# PowerLatch.net
KiCad netlist of a schematic drawn in Altium Designer
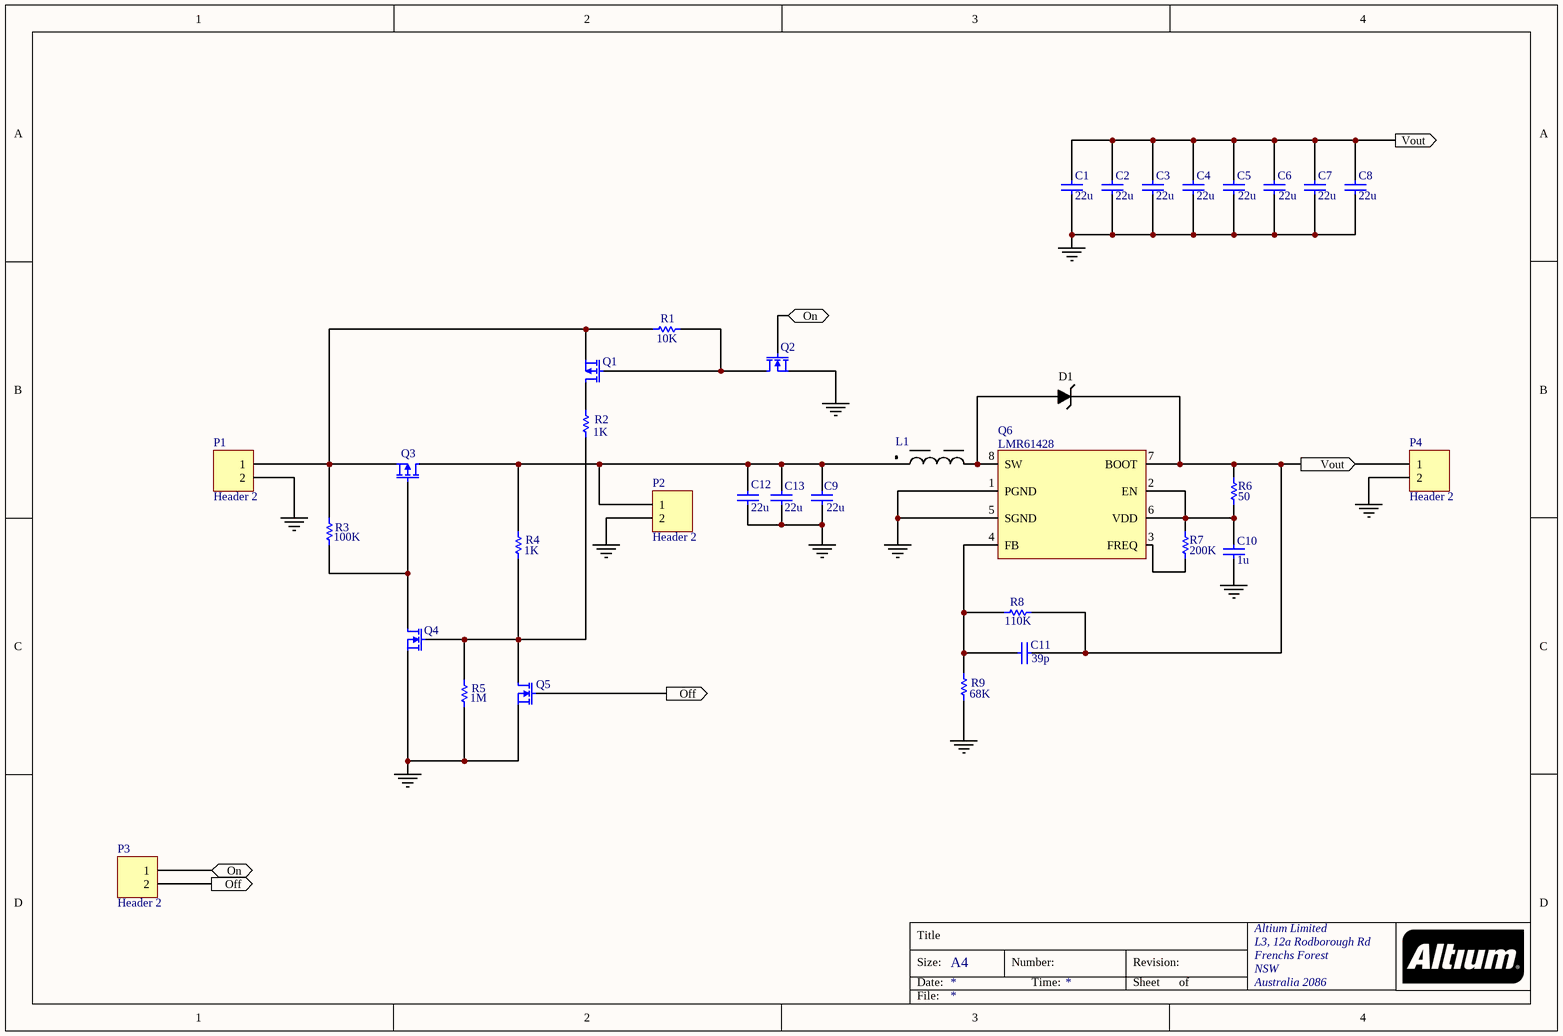
[diagram p0: PowerLatch.SchDoc]

(export (version "E")
  (design (tool "Eeschema 10.0.6"))
  (components
    (comp (ref "C1")
      (value "22u")
      (footprint "CAPC3225X28N")
      (description "Capacitor")
      (fields (field (name "Comment") "Cap") (field (name "PUBLISHER") "Altium Limited"))
      (libsource (lib "Miscellaneous Devices") (part "Cap"))
    )
    (comp (ref "C2")
      (value "22u")
      (footprint "CAPC3225X28N")
      (description "Capacitor")
      (fields (field (name "Comment") "Cap") (field (name "PUBLISHER") "Altium Limited"))
      (libsource (lib "Miscellaneous Devices") (part "Cap"))
    )
    (comp (ref "C3")
      (value "22u")
      (footprint "CAPC3225X28N")
      (description "Capacitor")
      (fields (field (name "Comment") "Cap") (field (name "PUBLISHER") "Altium Limited"))
      (libsource (lib "Miscellaneous Devices") (part "Cap"))
    )
    (comp (ref "C4")
      (value "22u")
      (footprint "CAPC3225X28N")
      (description "Capacitor")
      (fields (field (name "Comment") "Cap") (field (name "PUBLISHER") "Altium Limited"))
      (libsource (lib "Miscellaneous Devices") (part "Cap"))
    )
    (comp (ref "C5")
      (value "22u")
      (footprint "CAPC3225X28N")
      (description "Capacitor")
      (fields (field (name "Comment") "Cap") (field (name "PUBLISHER") "Altium Limited"))
      (libsource (lib "Miscellaneous Devices") (part "Cap"))
    )
    (comp (ref "C6")
      (value "22u")
      (footprint "CAPC3225X28N")
      (description "Capacitor")
      (fields (field (name "Comment") "Cap") (field (name "PUBLISHER") "Altium Limited"))
      (libsource (lib "Miscellaneous Devices") (part "Cap"))
    )
    (comp (ref "C7")
      (value "22u")
      (footprint "CAPC3225X28N")
      (description "Capacitor")
      (fields (field (name "Comment") "Cap") (field (name "PUBLISHER") "Altium Limited"))
      (libsource (lib "Miscellaneous Devices") (part "Cap"))
    )
    (comp (ref "C8")
      (value "22u")
      (footprint "CAPC3225X28N")
      (description "Capacitor")
      (fields (field (name "Comment") "Cap") (field (name "PUBLISHER") "Altium Limited"))
      (libsource (lib "Miscellaneous Devices") (part "Cap"))
    )
    (comp (ref "C9")
      (value "22u")
      (footprint "C1210_M")
      (description "Capacitor")
      (fields (field (name "Comment") "Cap") (field (name "PUBLISHER") "Altium Limited"))
      (libsource (lib "Miscellaneous Devices") (part "Cap"))
    )
    (comp (ref "C10")
      (value "1u")
      (footprint "C1210_M")
      (description "Capacitor")
      (fields (field (name "Comment") "Cap") (field (name "PUBLISHER") "Altium Limited"))
      (libsource (lib "Miscellaneous Devices") (part "Cap"))
    )
    (comp (ref "C11")
      (value "39p")
      (footprint "C1210_M")
      (description "Capacitor")
      (fields (field (name "Comment") "Cap") (field (name "PUBLISHER") "Altium Limited"))
      (libsource (lib "Miscellaneous Devices") (part "Cap"))
    )
    (comp (ref "C12")
      (value "22u")
      (footprint "C1210_M")
      (description "Capacitor")
      (fields (field (name "Comment") "Cap") (field (name "PUBLISHER") "Altium Limited"))
      (libsource (lib "Miscellaneous Devices") (part "Cap"))
    )
    (comp (ref "C13")
      (value "22u")
      (footprint "C1210_M")
      (description "Capacitor")
      (fields (field (name "Comment") "Cap") (field (name "PUBLISHER") "Altium Limited"))
      (libsource (lib "Miscellaneous Devices") (part "Cap"))
    )
    (comp (ref "D1")
      (value "Schottky")
      (footprint "DIOM4336X25N")
      (libsource (lib "Schlib1") (part "Schottky"))
    )
    (comp (ref "L1")
      (value "Inductor")
      (footprint "INDP120120X100N")
      (libsource (lib "Schlib1") (part "Inductor"))
    )
    (comp (ref "P1")
      (value "Header 2")
      (footprint "HDR1X2")
      (description "Header, 2-Pin")
      (fields (field (name "PUBLISHER") "Altium Limited"))
      (libsource (lib "Miscellaneous Connectors") (part "Header 2"))
    )
    (comp (ref "P2")
      (value "Header 2")
      (footprint "HDR1X2")
      (description "Header, 2-Pin")
      (fields (field (name "PUBLISHER") "Altium Limited"))
      (libsource (lib "") (part "Header 2_1"))
    )
    (comp (ref "P3")
      (value "Header 2")
      (footprint "HDR1X2")
      (description "Header, 2-Pin")
      (fields (field (name "PUBLISHER") "Altium Limited"))
      (libsource (lib "Miscellaneous Connectors") (part "Header 2"))
    )
    (comp (ref "P4")
      (value "Header 2")
      (footprint "HDR1X2")
      (description "Header, 2-Pin")
      (fields (field (name "PUBLISHER") "Altium Limited"))
      (libsource (lib "") (part "Header 2_1"))
    )
    (comp (ref "Q1")
      (value "MOSFET P-Channel")
      (footprint "SOT95P245X110-3N")
      (libsource (lib "Schlib1") (part "MOSFET P-Channel"))
    )
    (comp (ref "Q2")
      (value "MOSFET N-Channel")
      (footprint "SOT95P245X110-3N")
      (libsource (lib "Schlib1") (part "MOSFET N-Channel"))
    )
    (comp (ref "Q3")
      (value "MOSFET P-Channel")
      (footprint "SOT95P245X110-3N")
      (libsource (lib "Schlib1") (part "MOSFET P-Channel"))
    )
    (comp (ref "Q4")
      (value "MOSFET N-Channel")
      (footprint "SOT95P245X110-3N")
      (libsource (lib "Schlib1") (part "MOSFET N-Channel"))
    )
    (comp (ref "Q5")
      (value "MOSFET N-Channel")
      (footprint "SOT95P245X110-3N")
      (libsource (lib "Schlib1") (part "MOSFET N-Channel"))
    )
    (comp (ref "Q6")
      (value "LMR61428")
      (footprint "TSOP65P490X110-8N")
      (description "Step-Up Voltage Regulator")
      (libsource (lib "Schlib1") (part "LMR61428"))
    )
    (comp (ref "R1")
      (value "10K")
      (footprint "RESC1608X06N")
      (description "Resistor")
      (fields (field (name "Comment") "Res1") (field (name "PUBLISHER") "Altium Limited"))
      (libsource (lib "Miscellaneous Devices") (part "Res1"))
    )
    (comp (ref "R2")
      (value "1K")
      (footprint "RESC1608X06N")
      (description "Resistor")
      (fields (field (name "Comment") "Res1") (field (name "PUBLISHER") "Altium Limited"))
      (libsource (lib "Miscellaneous Devices") (part "Res1"))
    )
    (comp (ref "R3")
      (value "100K")
      (footprint "RESC1608X06N")
      (description "Resistor")
      (fields (field (name "Comment") "Res1") (field (name "PUBLISHER") "Altium Limited"))
      (libsource (lib "Miscellaneous Devices") (part "Res1"))
    )
    (comp (ref "R4")
      (value "1K")
      (footprint "RESC1608X06N")
      (description "Resistor")
      (fields (field (name "Comment") "Res1") (field (name "PUBLISHER") "Altium Limited"))
      (libsource (lib "Miscellaneous Devices") (part "Res1"))
    )
    (comp (ref "R5")
      (value "1M")
      (footprint "RESC1608X06N")
      (description "Resistor")
      (fields (field (name "Comment") "Res1") (field (name "PUBLISHER") "Altium Limited"))
      (libsource (lib "Miscellaneous Devices") (part "Res1"))
    )
    (comp (ref "R6")
      (value "50")
      (footprint "RESC1608X06N")
      (description "Resistor")
      (fields (field (name "Comment") "Res1") (field (name "PUBLISHER") "Altium Limited"))
      (libsource (lib "Miscellaneous Devices") (part "Res1"))
    )
    (comp (ref "R7")
      (value "200K")
      (footprint "RESC1608X06N")
      (description "Resistor")
      (fields (field (name "Comment") "Res1") (field (name "PUBLISHER") "Altium Limited"))
      (libsource (lib "Miscellaneous Devices") (part "Res1"))
    )
    (comp (ref "R8")
      (value "110K")
      (footprint "RESC1608X06N")
      (description "Resistor")
      (fields (field (name "Comment") "Res1") (field (name "PUBLISHER") "Altium Limited"))
      (libsource (lib "Miscellaneous Devices") (part "Res1"))
    )
    (comp (ref "R9")
      (value "68K")
      (footprint "RESC1608X06N")
      (description "Resistor")
      (fields (field (name "Comment") "Res1") (field (name "PUBLISHER") "Altium Limited"))
      (libsource (lib "Miscellaneous Devices") (part "Res1"))
    )
  )
  (nets
    (net (code "1") (name "/Off") (class "Default")
      (node (ref "P3") (pin "2") (pinfunction "2_2") (pintype "passive"))
      (node (ref "Q5") (pin "1") (pinfunction "G_1") (pintype "passive"))
    )
    (net (code "2") (name "/On") (class "Default")
      (node (ref "P3") (pin "1") (pinfunction "1_1") (pintype "passive"))
      (node (ref "Q2") (pin "1") (pinfunction "G_1") (pintype "passive"))
    )
    (net (code "3") (name "/Vout") (class "Default")
      (node (ref "C1") (pin "2") (pinfunction "2_2") (pintype "passive"))
      (node (ref "C11") (pin "1") (pinfunction "1_1") (pintype "passive"))
      (node (ref "C2") (pin "2") (pinfunction "2_2") (pintype "passive"))
      (node (ref "C3") (pin "2") (pinfunction "2_2") (pintype "passive"))
      (node (ref "C4") (pin "2") (pinfunction "2_2") (pintype "passive"))
      (node (ref "C5") (pin "2") (pinfunction "2_2") (pintype "passive"))
      (node (ref "C6") (pin "2") (pinfunction "2_2") (pintype "passive"))
      (node (ref "C7") (pin "2") (pinfunction "2_2") (pintype "passive"))
      (node (ref "C8") (pin "2") (pinfunction "2_2") (pintype "passive"))
      (node (ref "D1") (pin "2") (pinfunction "K_2") (pintype "passive"))
      (node (ref "P4") (pin "1") (pinfunction "1_1") (pintype "passive"))
      (node (ref "Q6") (pin "7") (pinfunction "BOOT_7") (pintype "passive"))
      (node (ref "R6") (pin "1") (pinfunction "1_1") (pintype "passive"))
      (node (ref "R8") (pin "2") (pinfunction "2_2") (pintype "passive"))
    )
    (net (code "4") (name "GND") (class "Default")
      (node (ref "C1") (pin "1") (pinfunction "1_1") (pintype "passive"))
      (node (ref "C10") (pin "1") (pinfunction "1_1") (pintype "passive"))
      (node (ref "C12") (pin "2") (pinfunction "2_2") (pintype "passive"))
      (node (ref "C13") (pin "2") (pinfunction "2_2") (pintype "passive"))
      (node (ref "C2") (pin "1") (pinfunction "1_1") (pintype "passive"))
      (node (ref "C3") (pin "1") (pinfunction "1_1") (pintype "passive"))
      (node (ref "C4") (pin "1") (pinfunction "1_1") (pintype "passive"))
      (node (ref "C5") (pin "1") (pinfunction "1_1") (pintype "passive"))
      (node (ref "C6") (pin "1") (pinfunction "1_1") (pintype "passive"))
      (node (ref "C7") (pin "1") (pinfunction "1_1") (pintype "passive"))
      (node (ref "C8") (pin "1") (pinfunction "1_1") (pintype "passive"))
      (node (ref "C9") (pin "2") (pinfunction "2_2") (pintype "passive"))
      (node (ref "P1") (pin "2") (pinfunction "2_2") (pintype "passive"))
      (node (ref "P2") (pin "2") (pinfunction "2_2") (pintype "passive"))
      (node (ref "P4") (pin "2") (pinfunction "2_2") (pintype "passive"))
      (node (ref "Q2") (pin "2") (pinfunction "S_2") (pintype "passive"))
      (node (ref "Q4") (pin "2") (pinfunction "S_2") (pintype "passive"))
      (node (ref "Q5") (pin "2") (pinfunction "S_2") (pintype "passive"))
      (node (ref "Q6") (pin "1") (pinfunction "PGND_1") (pintype "passive"))
      (node (ref "Q6") (pin "5") (pinfunction "SGND_5") (pintype "passive"))
      (node (ref "R5") (pin "1") (pinfunction "1_1") (pintype "passive"))
      (node (ref "R9") (pin "2") (pinfunction "2_2") (pintype "passive"))
    )
    (net (code "5") (name "Net-(D1-A)") (class "Default")
      (node (ref "D1") (pin "1") (pinfunction "A_1") (pintype "passive"))
      (node (ref "L1") (pin "2") (pinfunction "2_2") (pintype "passive"))
      (node (ref "Q6") (pin "8") (pinfunction "SW_8") (pintype "passive"))
    )
    (net (code "6") (name "Net-(Q1-D)") (class "Default")
      (node (ref "Q1") (pin "3") (pinfunction "D_3") (pintype "passive"))
      (node (ref "R2") (pin "2") (pinfunction "2_2") (pintype "passive"))
    )
    (net (code "7") (name "Net-(Q1-G)") (class "Default")
      (node (ref "Q1") (pin "1") (pinfunction "G_1") (pintype "passive"))
      (node (ref "Q2") (pin "3") (pinfunction "D_3") (pintype "passive"))
      (node (ref "R1") (pin "1") (pinfunction "1_1") (pintype "passive"))
    )
    (net (code "8") (name "Net-(Q1-S)") (class "Default")
      (node (ref "P1") (pin "1") (pinfunction "1_1") (pintype "passive"))
      (node (ref "Q1") (pin "2") (pinfunction "S_2") (pintype "passive"))
      (node (ref "Q3") (pin "2") (pinfunction "S_2") (pintype "passive"))
      (node (ref "R1") (pin "2") (pinfunction "2_2") (pintype "passive"))
      (node (ref "R3") (pin "2") (pinfunction "2_2") (pintype "passive"))
    )
    (net (code "9") (name "Net-(Q3-D)") (class "Default")
      (node (ref "C12") (pin "1") (pinfunction "1_1") (pintype "passive"))
      (node (ref "C13") (pin "1") (pinfunction "1_1") (pintype "passive"))
      (node (ref "C9") (pin "1") (pinfunction "1_1") (pintype "passive"))
      (node (ref "L1") (pin "1") (pinfunction "1_1") (pintype "passive"))
      (node (ref "P2") (pin "1") (pinfunction "1_1") (pintype "passive"))
      (node (ref "Q3") (pin "3") (pinfunction "D_3") (pintype "passive"))
      (node (ref "R4") (pin "2") (pinfunction "2_2") (pintype "passive"))
    )
    (net (code "10") (name "Net-(Q3-G)") (class "Default")
      (node (ref "Q3") (pin "1") (pinfunction "G_1") (pintype "passive"))
      (node (ref "Q4") (pin "3") (pinfunction "D_3") (pintype "passive"))
      (node (ref "R3") (pin "1") (pinfunction "1_1") (pintype "passive"))
    )
    (net (code "11") (name "Net-(Q4-G)") (class "Default")
      (node (ref "Q4") (pin "1") (pinfunction "G_1") (pintype "passive"))
      (node (ref "Q5") (pin "3") (pinfunction "D_3") (pintype "passive"))
      (node (ref "R2") (pin "1") (pinfunction "1_1") (pintype "passive"))
      (node (ref "R4") (pin "1") (pinfunction "1_1") (pintype "passive"))
      (node (ref "R5") (pin "2") (pinfunction "2_2") (pintype "passive"))
    )
    (net (code "12") (name "Net-(Q6-EN)") (class "Default")
      (node (ref "C10") (pin "2") (pinfunction "2_2") (pintype "passive"))
      (node (ref "Q6") (pin "2") (pinfunction "EN_2") (pintype "passive"))
      (node (ref "Q6") (pin "6") (pinfunction "VDD_6") (pintype "passive"))
      (node (ref "R6") (pin "2") (pinfunction "2_2") (pintype "passive"))
      (node (ref "R7") (pin "1") (pinfunction "1_1") (pintype "passive"))
    )
    (net (code "13") (name "Net-(Q6-FB)") (class "Default")
      (node (ref "C11") (pin "2") (pinfunction "2_2") (pintype "passive"))
      (node (ref "Q6") (pin "4") (pinfunction "FB_4") (pintype "passive"))
      (node (ref "R8") (pin "1") (pinfunction "1_1") (pintype "passive"))
      (node (ref "R9") (pin "1") (pinfunction "1_1") (pintype "passive"))
    )
    (net (code "14") (name "Net-(Q6-FREQ)") (class "Default")
      (node (ref "Q6") (pin "3") (pinfunction "FREQ_3") (pintype "passive"))
      (node (ref "R7") (pin "2") (pinfunction "2_2") (pintype "passive"))
    )
  )
)
